# ON_OFF_Controller.net
KiCad netlist of a schematic drawn in Altium Designer
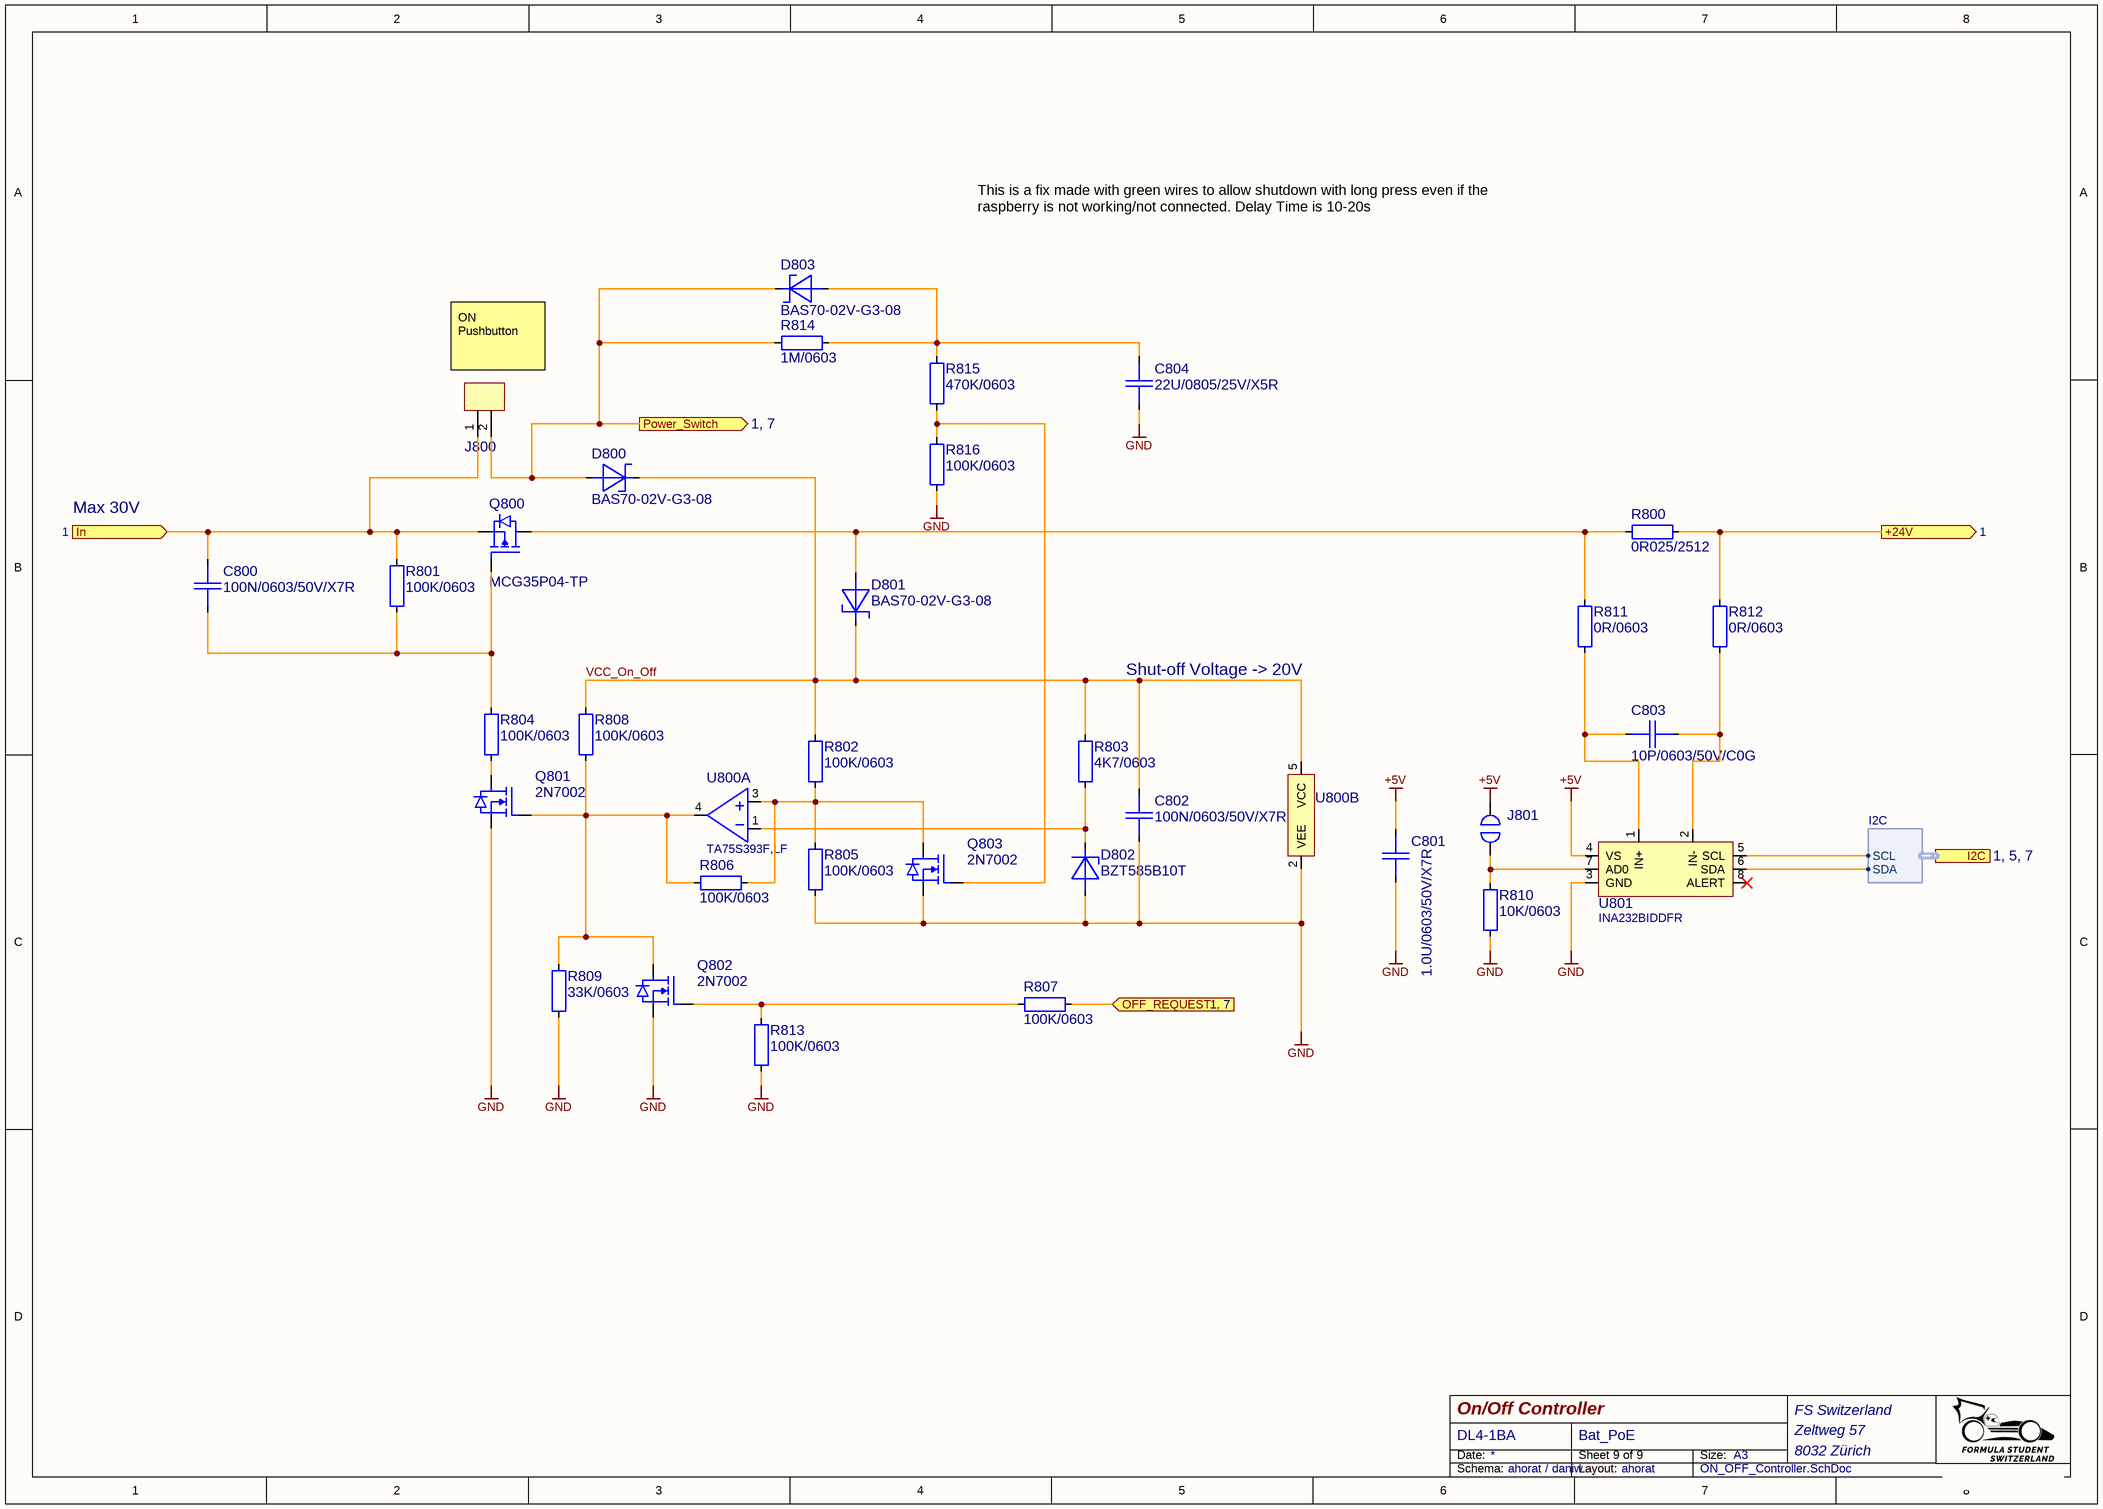
[diagram p0: ON_OFF_Controller.SchDoc]

(export (version "E")
  (design (tool "Eeschema 10.0.6"))
  (components
    (comp (ref "C800")
      (value "100N/0603/50V/X7R")
      (footprint "CAP0603_X7R")
      (description "CAP SM 0603 100nF 50V X7R")
      (fields (field (name "MANUFACTURER") "GENERIC"))
      (libsource (lib "daniw_altium_lib") (part "C"))
    )
    (comp (ref "C801")
      (value "1.0U/0603/50V/X7R")
      (footprint "CAP0603_X7R")
      (description "CAP SM 0603 1.0uF 50V X7R")
      (fields (field (name "MANUFACTURER") "GENERIC"))
      (libsource (lib "daniw_altium_lib") (part "C"))
    )
    (comp (ref "C802")
      (value "100N/0603/50V/X7R")
      (footprint "CAP0603_X7R")
      (description "CAP SM 0603 100nF 50V X7R")
      (fields (field (name "MANUFACTURER") "GENERIC"))
      (libsource (lib "daniw_altium_lib") (part "C"))
    )
    (comp (ref "C803")
      (value "10P/0603/50V/C0G")
      (footprint "CAP0603_C0G")
      (description "CAP SM 0603 10pF 50V C0G")
      (fields (field (name "MANUFACTURER") "GENERIC"))
      (libsource (lib "daniw_altium_lib") (part "C"))
    )
    (comp (ref "C804")
      (value "22U/0805/25V/X5R")
      (footprint "CAP0805_X7R")
      (description "CAP SM 0805 22uF 25V X5R")
      (fields (field (name "MANUFACTURER") "GENERIC"))
      (libsource (lib "daniw_altium_lib") (part "C"))
    )
    (comp (ref "D800")
      (value "BAS70-02V-G3-08")
      (footprint "SOD1608X065")
      (description "Small Signal Schottky Diode")
      (fields (field (name "MANUFACTURER") "Vishay"))
      (libsource (lib "daniw_altium_lib") (part "D_Schottky"))
    )
    (comp (ref "D801")
      (value "BAS70-02V-G3-08")
      (footprint "SOD1608X065")
      (description "Small Signal Schottky Diode")
      (fields (field (name "MANUFACTURER") "Vishay"))
      (libsource (lib "daniw_altium_lib") (part "D_Schottky"))
    )
    (comp (ref "D802")
      (value "BZT585B10T")
      (footprint "SOD1608X065")
      (description "DIODE ZENER 10V 350MW SOD523")
      (fields (field (name "MANUFACTURER") "Diodes Incorporated"))
      (libsource (lib "daniw_altium_lib") (part "D_Zener"))
    )
    (comp (ref "D803")
      (value "BAS70-02V-G3-08")
      (footprint "SOD1608X065")
      (description "Small Signal Schottky Diode")
      (fields (field (name "MANUFACTURER") "Vishay"))
      (libsource (lib "daniw_altium_lib") (part "D_Schottky"))
    )
    (comp (ref "J800")
      (value "5600200220")
      (footprint "5600200220")
      (description "DuraClik Wire-to-Board Header, Single Row, Vertical, 2 Circuits, Tin (Sn) Over Nickel, Natural")
      (fields (field (name "PART NUMBER") "DuraClick_1x2_VERT_SMD") (field (name "MANUFACTURER") "Molex"))
      (libsource (lib "daniw_altium_lib") (part "CON2"))
    )
    (comp (ref "J801")
      (value "Solder Jumper 2pin 0.2mm small")
      (footprint "Solder_Jumper_2pin_0.2mm_small")
      (description "Solder jumper with two pins with a spacing of 0.2mm")
      (fields
        (field (name "PART NUMBER") "Solder_Jumper_2pin_0.2mm_small")
        (field (name "MANUFACTURER") "NONE")
      )
      (libsource (lib "daniw_altium_lib") (part "SolderJumper_2"))
    )
    (comp (ref "Q800")
      (value "MCG35P04-TP")
      (footprint "SON065P330X330X075-5-TH245X175")
      (description "40V 35A P-Channel MOSFET")
      (fields (field (name "MANUFACTURER") "Micro Commercial Co"))
      (libsource (lib "daniw_altium_lib") (part "MOSFET P"))
    )
    (comp (ref "Q801")
      (value "2N7002")
      (footprint "SOT2395P280X125-3-SE")
      (description "60V 115mA 1.2Ω@10V,500mA 200mW 2.1V@250uA N Channel SOT-23 MOSFETs")
      (fields (field (name "MANUFACTURER") "GENERIC"))
      (libsource (lib "daniw_altium_lib") (part "MOSFET N_SOT23"))
    )
    (comp (ref "Q802")
      (value "2N7002")
      (footprint "SOT2395P280X125-3-SE")
      (description "60V 115mA 1.2Ω@10V,500mA 200mW 2.1V@250uA N Channel SOT-23 MOSFETs")
      (fields (field (name "MANUFACTURER") "GENERIC"))
      (libsource (lib "daniw_altium_lib") (part "MOSFET N_SOT23"))
    )
    (comp (ref "Q803")
      (value "2N7002")
      (footprint "SOT2395P280X125-3-SE")
      (description "60V 115mA 1.2Ω@10V,500mA 200mW 2.1V@250uA N Channel SOT-23 MOSFETs")
      (fields (field (name "MANUFACTURER") "GENERIC"))
      (libsource (lib "daniw_altium_lib") (part "MOSFET N_SOT23"))
    )
    (comp (ref "R800")
      (value "0R025/2512")
      (footprint "R2512-0.65-WW")
      (description "RES SM 2512 0R025")
      (fields (field (name "MANUFACTURER") "GENERIC"))
      (libsource (lib "daniw_altium_lib") (part "R"))
    )
    (comp (ref "R801")
      (value "100K/0603")
      (footprint "R0603-0.40-WW")
      (description "RES SM 0603 100K")
      (fields (field (name "MANUFACTURER") "GENERIC"))
      (libsource (lib "daniw_altium_lib") (part "R"))
    )
    (comp (ref "R802")
      (value "100K/0603")
      (footprint "R0603-0.40-WW")
      (description "RES SM 0603 100K")
      (fields (field (name "MANUFACTURER") "GENERIC"))
      (libsource (lib "daniw_altium_lib") (part "R"))
    )
    (comp (ref "R803")
      (value "4K7/0603")
      (footprint "R0603-0.40-WW")
      (description "RES SM 0603 4K7")
      (fields (field (name "MANUFACTURER") "GENERIC"))
      (libsource (lib "daniw_altium_lib") (part "R"))
    )
    (comp (ref "R804")
      (value "100K/0603")
      (footprint "R0603-0.40-WW")
      (description "RES SM 0603 100K")
      (fields (field (name "MANUFACTURER") "GENERIC"))
      (libsource (lib "daniw_altium_lib") (part "R"))
    )
    (comp (ref "R805")
      (value "100K/0603")
      (footprint "R0603-0.40-WW")
      (description "RES SM 0603 100K")
      (fields (field (name "MANUFACTURER") "GENERIC"))
      (libsource (lib "daniw_altium_lib") (part "R"))
    )
    (comp (ref "R806")
      (value "100K/0603")
      (footprint "R0603-0.40-WW")
      (description "RES SM 0603 100K")
      (fields (field (name "MANUFACTURER") "GENERIC"))
      (libsource (lib "daniw_altium_lib") (part "R"))
    )
    (comp (ref "R807")
      (value "100K/0603")
      (footprint "R0603-0.40-WW")
      (description "RES SM 0603 100K")
      (fields (field (name "MANUFACTURER") "GENERIC"))
      (libsource (lib "daniw_altium_lib") (part "R"))
    )
    (comp (ref "R808")
      (value "100K/0603")
      (footprint "R0603-0.40-WW")
      (description "RES SM 0603 100K")
      (fields (field (name "MANUFACTURER") "GENERIC"))
      (libsource (lib "daniw_altium_lib") (part "R"))
    )
    (comp (ref "R809")
      (value "33K/0603")
      (footprint "R0603-0.40-WW")
      (description "RES SM 0603 33K")
      (fields (field (name "MANUFACTURER") "GENERIC"))
      (libsource (lib "daniw_altium_lib") (part "R"))
    )
    (comp (ref "R810")
      (value "10K/0603")
      (footprint "R0603-0.40-WW")
      (description "RES SM 0603 10K")
      (fields (field (name "MANUFACTURER") "GENERIC"))
      (libsource (lib "daniw_altium_lib") (part "R"))
    )
    (comp (ref "R811")
      (value "0R/0603")
      (footprint "R0603-0.40-WW")
      (description "RES SM 0603 0R")
      (fields (field (name "MANUFACTURER") "GENERIC"))
      (libsource (lib "daniw_altium_lib") (part "R"))
    )
    (comp (ref "R812")
      (value "0R/0603")
      (footprint "R0603-0.40-WW")
      (description "RES SM 0603 0R")
      (fields (field (name "MANUFACTURER") "GENERIC"))
      (libsource (lib "daniw_altium_lib") (part "R"))
    )
    (comp (ref "R813")
      (value "100K/0603")
      (footprint "R0603-0.40-WW")
      (description "RES SM 0603 100K")
      (fields (field (name "MANUFACTURER") "GENERIC"))
      (libsource (lib "daniw_altium_lib") (part "R"))
    )
    (comp (ref "R814")
      (value "1M/0603")
      (footprint "R0603-0.40-WW")
      (description "RES SM 0603 1M")
      (fields (field (name "MANUFACTURER") "GENERIC"))
      (libsource (lib "daniw_altium_lib") (part "R"))
    )
    (comp (ref "R815")
      (value "470K/0603")
      (footprint "R0603-0.40-WW")
      (description "RES SM 0603 470K")
      (fields (field (name "MANUFACTURER") "GENERIC"))
      (libsource (lib "daniw_altium_lib") (part "R"))
    )
    (comp (ref "R816")
      (value "100K/0603")
      (footprint "R0603-0.40-WW")
      (description "RES SM 0603 100K")
      (fields (field (name "MANUFACTURER") "GENERIC"))
      (libsource (lib "daniw_altium_lib") (part "R"))
    )
    (comp (ref "U800")
      (value "TA75S393F,LF")
      (footprint "SOT2395P280X125-5-SW")
      (description "36V Single Voltage Comparator")
      (fields (field (name "MANUFACTURER") "Toshiba Semiconductor and Storage"))
      (libsource (lib "daniw_altium_lib") (part "OPA_SOT23"))
    )
    (comp (ref "U801")
      (value "INA232BIDDFR")
      (footprint "SOT065P280X110-8-SE")
      (description "INA232 48-V, 16-Bit, Current, Voltage, and Power Monitor With an I2C Interface")
      (fields (field (name "MANUFACTURER") "Texas Instruments"))
      (libsource (lib "daniw_altium_lib") (part "INA232"))
    )
  )
  (nets
    (net (code "2") (name "+5V") (class "Default")
      (node (ref "C801") (pin "1") (pinfunction "1_1") (pintype "passive"))
      (node (ref "J801") (pin "1") (pinfunction "1_1") (pintype "passive"))
      (node (ref "U801") (pin "4") (pinfunction "VS_4") (pintype "passive"))
    )
    (net (code "3") (name "/+24V") (class "Default")
      (node (ref "R800") (pin "2") (pinfunction "2_2") (pintype "passive"))
      (node (ref "R812") (pin "1") (pinfunction "1_1") (pintype "passive"))
    )
    (net (code "4") (name "/In") (class "Default")
      (node (ref "C800") (pin "1") (pinfunction "1_1") (pintype "passive"))
      (node (ref "J800") (pin "1") (pintype "passive"))
      (node (ref "Q800") (pin "S") (pinfunction "SOURCE_S") (pintype "passive"))
      (node (ref "R801") (pin "1") (pinfunction "1_1") (pintype "passive"))
    )
    (net (code "5") (name "/OFF_REQUEST") (class "Default")
      (node (ref "R807") (pin "1") (pinfunction "1_1") (pintype "passive"))
    )
    (net (code "6") (name "/Power_Switch") (class "Default")
      (node (ref "D800") (pin "2") (pinfunction "2_2") (pintype "passive"))
      (node (ref "D803") (pin "1") (pinfunction "1_1") (pintype "passive"))
      (node (ref "J800") (pin "2") (pintype "passive"))
      (node (ref "R814") (pin "1") (pinfunction "1_1") (pintype "passive"))
    )
    (net (code "7") (name "/SCL") (class "Default")
      (node (ref "U801") (pin "5") (pinfunction "SCL_5") (pintype "passive"))
    )
    (net (code "8") (name "/SDA") (class "Default")
      (node (ref "U801") (pin "6") (pinfunction "SDA_6") (pintype "passive"))
    )
    (net (code "9") (name "/VCC_On_Off") (class "Default")
      (node (ref "C802") (pin "1") (pinfunction "1_1") (pintype "passive"))
      (node (ref "D800") (pin "1") (pinfunction "1_1") (pintype "passive"))
      (node (ref "D801") (pin "1") (pinfunction "1_1") (pintype "passive"))
      (node (ref "R802") (pin "1") (pinfunction "1_1") (pintype "passive"))
      (node (ref "R803") (pin "1") (pinfunction "1_1") (pintype "passive"))
      (node (ref "R808") (pin "1") (pinfunction "1_1") (pintype "passive"))
      (node (ref "U800") (pin "5") (pinfunction "VCC_5") (pintype "passive"))
    )
    (net (code "11") (name "GND") (class "Default")
      (node (ref "C801") (pin "2") (pinfunction "2_2") (pintype "passive"))
      (node (ref "C802") (pin "2") (pinfunction "2_2") (pintype "passive"))
      (node (ref "C804") (pin "2") (pinfunction "2_2") (pintype "passive"))
      (node (ref "D802") (pin "2") (pinfunction "2_2") (pintype "passive"))
      (node (ref "Q801") (pin "2") (pinfunction "SOURCE_2") (pintype "passive"))
      (node (ref "Q802") (pin "2") (pinfunction "SOURCE_2") (pintype "passive"))
      (node (ref "Q803") (pin "2") (pinfunction "SOURCE_2") (pintype "passive"))
      (node (ref "R805") (pin "2") (pinfunction "2_2") (pintype "passive"))
      (node (ref "R809") (pin "2") (pinfunction "2_2") (pintype "passive"))
      (node (ref "R810") (pin "2") (pinfunction "2_2") (pintype "passive"))
      (node (ref "R813") (pin "2") (pinfunction "2_2") (pintype "passive"))
      (node (ref "R816") (pin "2") (pinfunction "2_2") (pintype "passive"))
      (node (ref "U800") (pin "2") (pinfunction "VEE_2") (pintype "passive"))
      (node (ref "U801") (pin "3") (pinfunction "GND_3") (pintype "passive"))
    )
    (net (code "12") (name "Net-(C804-Pad1)") (class "Default")
      (node (ref "C804") (pin "1") (pinfunction "1_1") (pintype "passive"))
      (node (ref "D803") (pin "2") (pinfunction "2_2") (pintype "passive"))
      (node (ref "R814") (pin "2") (pinfunction "2_2") (pintype "passive"))
      (node (ref "R815") (pin "2") (pinfunction "2_2") (pintype "passive"))
    )
    (net (code "13") (name "Net-(Q800-DRAIN)") (class "Default")
      (node (ref "D801") (pin "2") (pinfunction "2_2") (pintype "passive"))
      (node (ref "Q800") (pin "D") (pinfunction "DRAIN_D") (pintype "passive"))
      (node (ref "R800") (pin "1") (pinfunction "1_1") (pintype "passive"))
      (node (ref "R811") (pin "1") (pinfunction "1_1") (pintype "passive"))
    )
    (net (code "14") (name "Net-(Q800-GATE)") (class "Default")
      (node (ref "C800") (pin "2") (pinfunction "2_2") (pintype "passive"))
      (node (ref "Q800") (pin "G") (pinfunction "GATE_G") (pintype "passive"))
      (node (ref "R801") (pin "2") (pinfunction "2_2") (pintype "passive"))
      (node (ref "R804") (pin "1") (pinfunction "1_1") (pintype "passive"))
    )
    (net (code "15") (name "Net-(Q801-DRAIN)") (class "Default")
      (node (ref "Q801") (pin "3") (pinfunction "DRAIN_3") (pintype "passive"))
      (node (ref "R804") (pin "2") (pinfunction "2_2") (pintype "passive"))
    )
    (net (code "16") (name "Net-(Q801-GATE)") (class "Default")
      (node (ref "Q801") (pin "1") (pinfunction "GATE_1") (pintype "passive"))
      (node (ref "Q802") (pin "3") (pinfunction "DRAIN_3") (pintype "passive"))
      (node (ref "R806") (pin "2") (pinfunction "2_2") (pintype "passive"))
      (node (ref "R808") (pin "2") (pinfunction "2_2") (pintype "passive"))
      (node (ref "R809") (pin "1") (pinfunction "1_1") (pintype "passive"))
      (node (ref "U800") (pin "4") (pinfunction "OUT_4") (pintype "passive"))
    )
    (net (code "17") (name "Net-(Q802-GATE)") (class "Default")
      (node (ref "Q802") (pin "1") (pinfunction "GATE_1") (pintype "passive"))
      (node (ref "R807") (pin "2") (pinfunction "2_2") (pintype "passive"))
      (node (ref "R813") (pin "1") (pinfunction "1_1") (pintype "passive"))
    )
    (net (code "18") (name "Net-(Q803-DRAIN)") (class "Default")
      (node (ref "Q803") (pin "3") (pinfunction "DRAIN_3") (pintype "passive"))
      (node (ref "R802") (pin "2") (pinfunction "2_2") (pintype "passive"))
      (node (ref "R805") (pin "1") (pinfunction "1_1") (pintype "passive"))
      (node (ref "R806") (pin "1") (pinfunction "1_1") (pintype "passive"))
      (node (ref "U800") (pin "3") (pinfunction "IN+_3") (pintype "passive"))
    )
    (net (code "19") (name "Net-(Q803-GATE)") (class "Default")
      (node (ref "Q803") (pin "1") (pinfunction "GATE_1") (pintype "passive"))
      (node (ref "R815") (pin "1") (pinfunction "1_1") (pintype "passive"))
      (node (ref "R816") (pin "1") (pinfunction "1_1") (pintype "passive"))
    )
    (net (code "20") (name "Net-(U800A-IN-)") (class "Default")
      (node (ref "D802") (pin "1") (pinfunction "1_1") (pintype "passive"))
      (node (ref "R803") (pin "2") (pinfunction "2_2") (pintype "passive"))
      (node (ref "U800") (pin "1") (pinfunction "IN-_1") (pintype "passive"))
    )
    (net (code "21") (name "Net-(U801-AD0)") (class "Default")
      (node (ref "J801") (pin "2") (pinfunction "2_2") (pintype "passive"))
      (node (ref "R810") (pin "1") (pinfunction "1_1") (pintype "passive"))
      (node (ref "U801") (pin "7") (pinfunction "AD0_7") (pintype "passive"))
    )
    (net (code "22") (name "Net-(U801-IN+)") (class "Default")
      (node (ref "C803") (pin "2") (pinfunction "2_2") (pintype "passive"))
      (node (ref "R811") (pin "2") (pinfunction "2_2") (pintype "passive"))
      (node (ref "U801") (pin "1") (pinfunction "IN+_1") (pintype "passive"))
    )
    (net (code "23") (name "Net-(U801-IN-)") (class "Default")
      (node (ref "C803") (pin "1") (pinfunction "1_1") (pintype "passive"))
      (node (ref "R812") (pin "2") (pinfunction "2_2") (pintype "passive"))
      (node (ref "U801") (pin "2") (pinfunction "IN-_2") (pintype "passive"))
    )
    (net (code "24") (name "unconnected-(U801-ALERT-Pad8)") (class "Default")
      (node (ref "U801") (pin "8") (pinfunction "ALERT_8") (pintype "passive+no_connect"))
    )
  )
)
